# Interface_BUS.net
KiCad netlist of a schematic drawn in Altium Designer
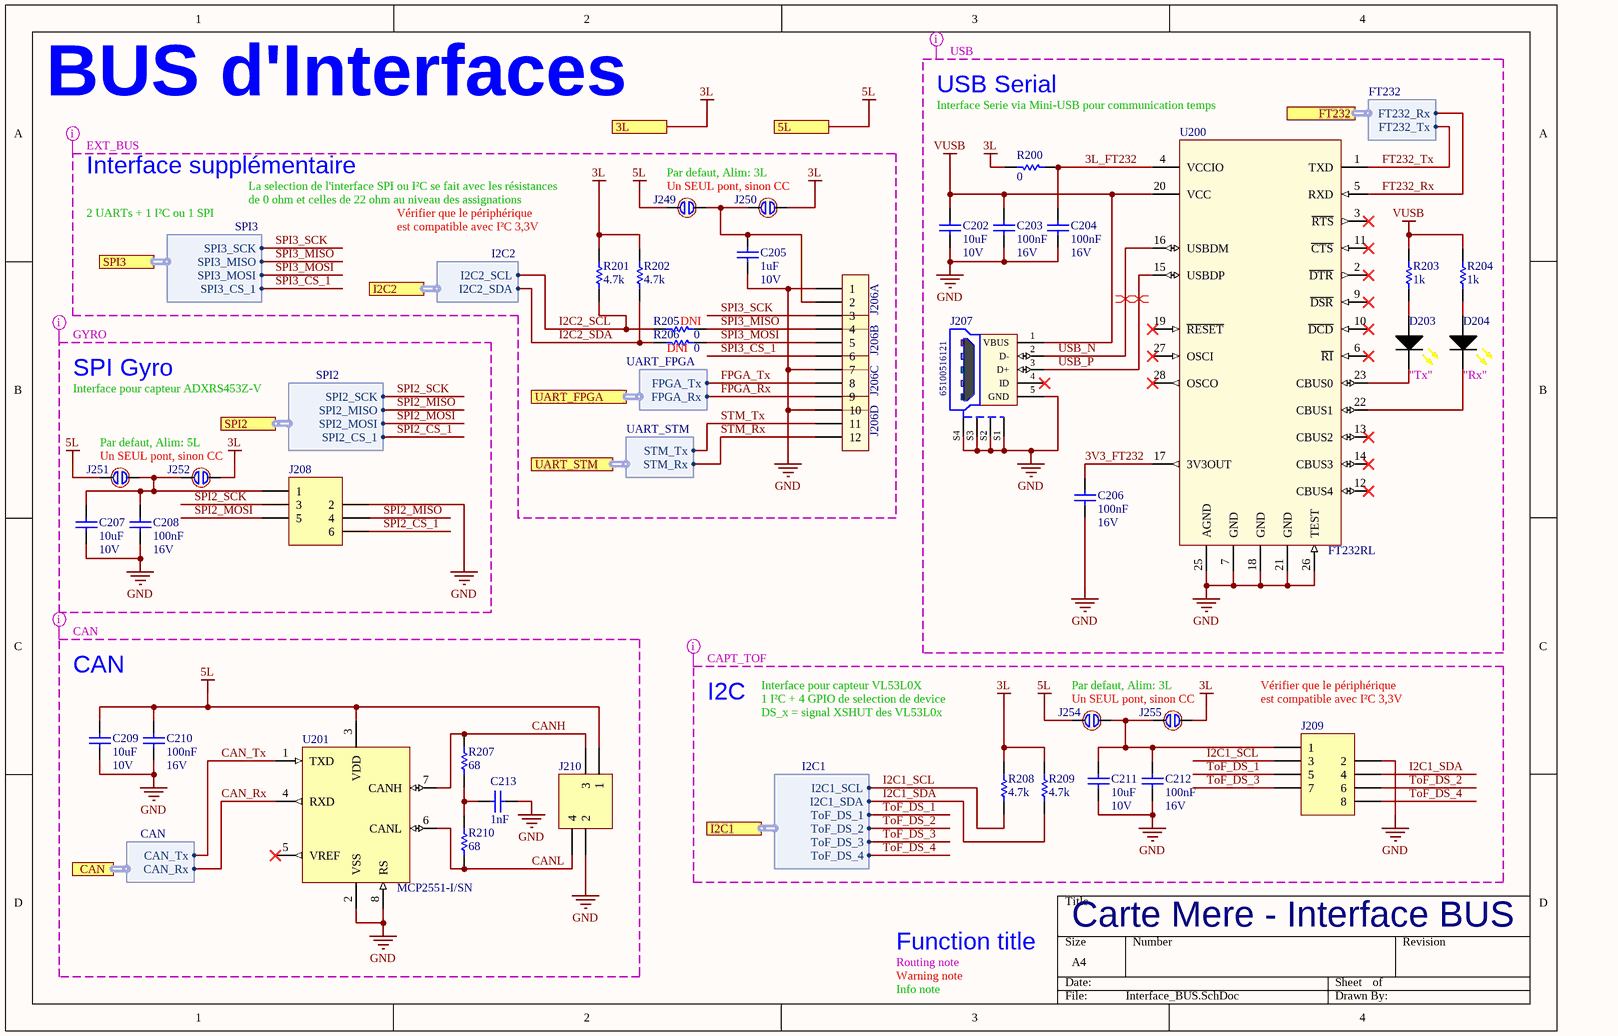
[diagram p0: Interface_BUS.SchDoc]

(export (version "E")
  (design (tool "Eeschema 10.0.6"))
  (components
    (comp (ref "C202")
      (value "10uF")
      (footprint "WCAP-CSGP_0805, 2x1.25x1.25")
      (description "CAP CER 10uF 10V X7R 0805")
      (fields
        (field (name "MANUFACTURER") "Wurth Elektronik")
        (field (name "MANUFACTURER PART NUMBER") "885012207026")
        (field (name "RATEDVOLTAGE") "10V")
      )
      (libsource (lib "Condensateur") (part "WCAP-CSGP, 885012207026"))
    )
    (comp (ref "C203")
      (value "100nF")
      (footprint "WCAP-CSGP_0402, 1x0.5x0.5")
      (description "CAP CER 100nF 16V X7R 0402")
      (fields
        (field (name "MANUFACTURER") "Wurth Elektronik")
        (field (name "MANUFACTURER PART NUMBER") "885012205037")
        (field (name "RATEDVOLTAGE") "16V")
      )
      (libsource (lib "Condensateur") (part "WCAP-CSGP, 885012205037"))
    )
    (comp (ref "C204")
      (value "100nF")
      (footprint "WCAP-CSGP_0402, 1x0.5x0.5")
      (description "CAP CER 100nF 16V X7R 0402")
      (fields
        (field (name "MANUFACTURER") "Wurth Elektronik")
        (field (name "MANUFACTURER PART NUMBER") "885012205037")
        (field (name "RATEDVOLTAGE") "16V")
      )
      (libsource (lib "Condensateur") (part "WCAP-CSGP, 885012205037"))
    )
    (comp (ref "C205")
      (value "1uF")
      (footprint "WCAP-CSGP_0402, 1x0.5x0.5")
      (description "CAP CER 1UF 10V X5R 0402")
      (fields
        (field (name "MANUFACTURER") "Wurth Elektronik")
        (field (name "MANUFACTURER PART NUMBER") "885012105012")
        (field (name "RATEDVOLTAGE") "10V")
      )
      (libsource (lib "Condensateur") (part "WCAP-CSGP, 885012105012"))
    )
    (comp (ref "C206")
      (value "100nF")
      (footprint "WCAP-CSGP_0402, 1x0.5x0.5")
      (description "CAP CER 100nF 16V X7R 0402")
      (fields
        (field (name "MANUFACTURER") "Wurth Elektronik")
        (field (name "MANUFACTURER PART NUMBER") "885012205037")
        (field (name "RATEDVOLTAGE") "16V")
      )
      (libsource (lib "Condensateur") (part "WCAP-CSGP, 885012205037"))
    )
    (comp (ref "C207")
      (value "10uF")
      (footprint "WCAP-CSGP_0805, 2x1.25x1.25")
      (description "CAP CER 10uF 10V X7R 0805")
      (fields
        (field (name "MANUFACTURER") "Wurth Elektronik")
        (field (name "MANUFACTURER PART NUMBER") "885012207026")
        (field (name "RATEDVOLTAGE") "10V")
      )
      (libsource (lib "Condensateur") (part "WCAP-CSGP, 885012207026"))
    )
    (comp (ref "C208")
      (value "100nF")
      (footprint "WCAP-CSGP_0402, 1x0.5x0.5")
      (description "CAP CER 100nF 16V X7R 0402")
      (fields
        (field (name "MANUFACTURER") "Wurth Elektronik")
        (field (name "MANUFACTURER PART NUMBER") "885012205037")
        (field (name "RATEDVOLTAGE") "16V")
      )
      (libsource (lib "Condensateur") (part "WCAP-CSGP, 885012205037"))
    )
    (comp (ref "C209")
      (value "10uF")
      (footprint "WCAP-CSGP_0805, 2x1.25x1.25")
      (description "CAP CER 10uF 10V X7R 0805")
      (fields
        (field (name "MANUFACTURER") "Wurth Elektronik")
        (field (name "MANUFACTURER PART NUMBER") "885012207026")
        (field (name "RATEDVOLTAGE") "10V")
      )
      (libsource (lib "Condensateur") (part "WCAP-CSGP, 885012207026"))
    )
    (comp (ref "C210")
      (value "100nF")
      (footprint "WCAP-CSGP_0402, 1x0.5x0.5")
      (description "CAP CER 100nF 16V X7R 0402")
      (fields
        (field (name "MANUFACTURER") "Wurth Elektronik")
        (field (name "MANUFACTURER PART NUMBER") "885012205037")
        (field (name "RATEDVOLTAGE") "16V")
      )
      (libsource (lib "Condensateur") (part "WCAP-CSGP, 885012205037"))
    )
    (comp (ref "C211")
      (value "10uF")
      (footprint "WCAP-CSGP_0805, 2x1.25x1.25")
      (description "CAP CER 10uF 10V X7R 0805")
      (fields
        (field (name "MANUFACTURER") "Wurth Elektronik")
        (field (name "MANUFACTURER PART NUMBER") "885012207026")
        (field (name "RATEDVOLTAGE") "10V")
      )
      (libsource (lib "Condensateur") (part "WCAP-CSGP, 885012207026"))
    )
    (comp (ref "C212")
      (value "100nF")
      (footprint "WCAP-CSGP_0402, 1x0.5x0.5")
      (description "CAP CER 100nF 16V X7R 0402")
      (fields
        (field (name "MANUFACTURER") "Wurth Elektronik")
        (field (name "MANUFACTURER PART NUMBER") "885012205037")
        (field (name "RATEDVOLTAGE") "16V")
      )
      (libsource (lib "Condensateur") (part "WCAP-CSGP, 885012205037"))
    )
    (comp (ref "C213")
      (value "1nF")
      (footprint "WCAP-CSGP_0402, 1x0.5x0.5")
      (description "CAP CER 1nF 50V X7R 0402")
      (fields
        (field (name "MANUFACTURER") "Wurth Elektronik")
        (field (name "MANUFACTURER PART NUMBER") "885012205061")
      )
      (libsource (lib "Condensateur") (part "WCAP-CSGP, 885012205061"))
    )
    (comp (ref "D203")
      (value "150060YS75000")
      (footprint "SMCW_0603")
      (description "SMD mono-color Chip LED, WL-SMCW, Yellow")
      (fields (field (name "MANUFACTURER") "Wurth Elektronik"))
      (libsource (lib "Opto") (part "WL-SMCW 0603  150060YS75000"))
    )
    (comp (ref "D204")
      (value "150060YS75000")
      (footprint "SMCW_0603")
      (description "SMD mono-color Chip LED, WL-SMCW, Yellow")
      (fields (field (name "MANUFACTURER") "Wurth Elektronik"))
      (libsource (lib "Opto") (part "WL-SMCW 0603  150060YS75000"))
    )
    (comp (ref "J206")
      (value "TSW-104-08-F-T-RA")
      (footprint "TSW-104-08-F-T-RA")
      (description "CONN HEADER R/A 3L x 4POS 2.54MM")
      (fields (field (name "MANUFACTURER") "SAMTEC"))
      (libsource (lib "Connecteurs") (part "TSW-104-08-F-T-RA"))
    )
    (comp (ref "J207")
      (value "65100516121")
      (footprint "65100516121")
      (description "Mini USB 2.0 Type B, Receptacle, Horizontal, SMT")
      (fields (field (name "MANUFACTURER") "Wurth Elektronik"))
      (libsource (lib "Connecteurs") (part "65100516121"))
    )
    (comp (ref "J208")
      (value "690367280676")
      (footprint "690367280676")
      (description "WR-MM 6p Female SMT Connector with Polarization")
      (fields (field (name "MANUFACTURER") "Wurth Electronics Inc."))
      (libsource (lib "Connecteurs") (part "690367280676"))
    )
    (comp (ref "J209")
      (value "690367280876")
      (footprint "690367280876")
      (description "WR-MM 8p Female SMT Connector with Polarization")
      (fields (field (name "MANUFACTURER") "Wurth Electronics Inc."))
      (libsource (lib "Connecteurs") (part "690367280876"))
    )
    (comp (ref "J210")
      (value "690367280476")
      (footprint "690367280476")
      (description "WR-MM 4p Female SMT Connector with Polarization")
      (fields (field (name "MANUFACTURER") "Wurth Electronics Inc."))
      (libsource (lib "Connecteurs") (part "690367280476"))
    )
    (comp (ref "J249")
      (value "open")
      (footprint "CAVALIER")
      (description "Cavalier soudure \"ouvert\", pastille fendue 1.2mm")
      (libsource (lib "Divers") (part "CAVALIER_DOT"))
    )
    (comp (ref "J250")
      (value "open")
      (footprint "CAVALIER")
      (description "Cavalier soudure \"ouvert\", pastille fendue 1.2mm")
      (libsource (lib "Divers") (part "CAVALIER_DOT"))
    )
    (comp (ref "J251")
      (value "open")
      (footprint "CAVALIER")
      (description "Cavalier soudure \"ouvert\", pastille fendue 1.2mm")
      (libsource (lib "Divers") (part "CAVALIER_DOT"))
    )
    (comp (ref "J252")
      (value "open")
      (footprint "CAVALIER")
      (description "Cavalier soudure \"ouvert\", pastille fendue 1.2mm")
      (libsource (lib "Divers") (part "CAVALIER_DOT"))
    )
    (comp (ref "J254")
      (value "open")
      (footprint "CAVALIER")
      (description "Cavalier soudure \"ouvert\", pastille fendue 1.2mm")
      (libsource (lib "Divers") (part "CAVALIER_DOT"))
    )
    (comp (ref "J255")
      (value "open")
      (footprint "CAVALIER")
      (description "Cavalier soudure \"ouvert\", pastille fendue 1.2mm")
      (libsource (lib "Divers") (part "CAVALIER_DOT"))
    )
    (comp (ref "R200")
      (value "0")
      (footprint "RESC1608X06N")
      (description "RES SMD 0 OHM 1% 1/10W 0603")
      (fields
        (field (name "MANUFACTURER") "Yageo")
        (field (name "MANUFACTURER PART NUMBER") "RC0603FR-070RL")
      )
      (libsource (lib "Resistance") (part "RC0603FR-070RL"))
    )
    (comp (ref "R201")
      (value "4.7k")
      (footprint "RESC1005X04N")
      (description "RES SMD 4K7 OHM 1% 1/16W 0402")
      (fields (field (name "POWER") "63mW") (field (name "MANUFACTURER") "Yageo"))
      (libsource (lib "Resistance") (part "RC0402FR-074K7L"))
    )
    (comp (ref "R202")
      (value "4.7k")
      (footprint "RESC1005X04N")
      (description "RES SMD 4K7 OHM 1% 1/16W 0402")
      (fields (field (name "POWER") "63mW") (field (name "MANUFACTURER") "Yageo"))
      (libsource (lib "Resistance") (part "RC0402FR-074K7L"))
    )
    (comp (ref "R203")
      (value "1k")
      (footprint "RESC1005X04N")
      (description "RES SMD 1K OHM 1% 1/16W 0402")
      (fields (field (name "POWER") "63mW") (field (name "MANUFACTURER") "Yageo"))
      (libsource (lib "Resistance") (part "RC0402FR-071KL"))
    )
    (comp (ref "R204")
      (value "1k")
      (footprint "RESC1005X04N")
      (description "RES SMD 1K OHM 1% 1/16W 0402")
      (fields (field (name "POWER") "63mW") (field (name "MANUFACTURER") "Yageo"))
      (libsource (lib "Resistance") (part "RC0402FR-071KL"))
    )
    (comp (ref "R205")
      (value "0")
      (footprint "RESC1608X06N")
      (description "RES SMD 0 OHM 1% 1/10W 0603")
      (fields
        (field (name "MANUFACTURER") "Yageo")
        (field (name "MANUFACTURER PART NUMBER") "RC0603FR-070RL")
      )
      (libsource (lib "Resistance") (part "RC0603FR-070RL"))
    )
    (comp (ref "R206")
      (value "0")
      (footprint "RESC1608X06N")
      (description "RES SMD 0 OHM 1% 1/10W 0603")
      (fields
        (field (name "MANUFACTURER") "Yageo")
        (field (name "MANUFACTURER PART NUMBER") "RC0603FR-070RL")
      )
      (libsource (lib "Resistance") (part "RC0603FR-070RL"))
    )
    (comp (ref "R207")
      (value "68")
      (footprint "RESC1608X06N")
      (description "RES SMD 68 OHM 1% 1/10W 0603")
      (fields
        (field (name "MANUFACTURER") "Yageo")
        (field (name "MANUFACTURER PART NUMBER") "RC0603FR-0768RL")
      )
      (libsource (lib "Resistance") (part "RC0603FR-0768RL"))
    )
    (comp (ref "R208")
      (value "4.7k")
      (footprint "RESC1005X04N")
      (description "RES SMD 4K7 OHM 1% 1/16W 0402")
      (fields (field (name "POWER") "63mW") (field (name "MANUFACTURER") "Yageo"))
      (libsource (lib "Resistance") (part "RC0402FR-074K7L"))
    )
    (comp (ref "R209")
      (value "4.7k")
      (footprint "RESC1005X04N")
      (description "RES SMD 4K7 OHM 1% 1/16W 0402")
      (fields (field (name "POWER") "63mW") (field (name "MANUFACTURER") "Yageo"))
      (libsource (lib "Resistance") (part "RC0402FR-074K7L"))
    )
    (comp (ref "R210")
      (value "68")
      (footprint "RESC1608X06N")
      (description "RES SMD 68 OHM 1% 1/10W 0603")
      (fields
        (field (name "MANUFACTURER") "Yageo")
        (field (name "MANUFACTURER PART NUMBER") "RC0603FR-0768RL")
      )
      (libsource (lib "Resistance") (part "RC0603FR-0768RL"))
    )
    (comp (ref "U200")
      (value "FT232RL")
      (footprint "SSOP28")
      (description "USB VERS UART CMS SSOP28 232")
      (fields (field (name "MANUFACTURER") "FTDI"))
      (libsource (lib "CI") (part "FT232RL"))
    )
    (comp (ref "U201")
      (value "MCP2551-I/SN")
      (footprint "SOIC127P600X175-8N")
      (description "IC TRANSCEIVER CAN HI-SPD 8-SOIC")
      (fields (field (name "MANUFACTURER") "Microchip Technology"))
      (libsource (lib "CI") (part "MCP2551-I/SN"))
    )
  )
  (nets
    (net (code "9") (name "/3L_FT232") (class "Default")
      (node (ref "C204") (pin "1") (pinfunction "1_1") (pintype "passive"))
      (node (ref "R200") (pin "2") (pinfunction "2_2") (pintype "passive"))
      (node (ref "U200") (pin "4") (pinfunction "VCCIO_4") (pintype "power_in"))
    )
    (net (code "10") (name "/3V3_FT232") (class "Default")
      (node (ref "C206") (pin "1") (pinfunction "1_1") (pintype "passive"))
      (node (ref "U200") (pin "17") (pinfunction "3V3OUT_17") (pintype "output"))
    )
    (net (code "11") (name "/CANH") (class "Default")
      (node (ref "J210") (pin "3") (pinfunction "3_3") (pintype "passive"))
      (node (ref "R207") (pin "2") (pinfunction "2_2") (pintype "passive"))
      (node (ref "U201") (pin "7") (pinfunction "CANH_7") (pintype "bidirectional"))
    )
    (net (code "12") (name "/CANL") (class "Default")
      (node (ref "J210") (pin "4") (pinfunction "4_4") (pintype "passive"))
      (node (ref "R210") (pin "1") (pinfunction "1_1") (pintype "passive"))
      (node (ref "U201") (pin "6") (pinfunction "CANL_6") (pintype "bidirectional"))
    )
    (net (code "13") (name "/CAN_Rx") (class "Default")
      (node (ref "U201") (pin "4") (pinfunction "RXD_4") (pintype "output"))
    )
    (net (code "14") (name "/CAN_Tx") (class "Default")
      (node (ref "U201") (pin "1") (pinfunction "TXD_1") (pintype "input"))
    )
    (net (code "15") (name "/FPGA_Rx") (class "Default")
      (node (ref "J206") (pin "9") (pinfunction "9_9") (pintype "passive"))
    )
    (net (code "16") (name "/FPGA_Tx") (class "Default")
      (node (ref "J206") (pin "8") (pinfunction "8_8") (pintype "passive"))
    )
    (net (code "17") (name "/FT232_Rx") (class "Default")
      (node (ref "U200") (pin "5") (pinfunction "RXD_5") (pintype "input"))
    )
    (net (code "18") (name "/FT232_Tx") (class "Default")
      (node (ref "U200") (pin "1") (pinfunction "TXD_1") (pintype "passive"))
    )
    (net (code "19") (name "/I2C1_SCL") (class "Default")
      (node (ref "J209") (pin "3") (pinfunction "3_3") (pintype "passive"))
      (node (ref "R208") (pin "1") (pinfunction "1_1") (pintype "passive"))
    )
    (net (code "20") (name "/I2C1_SDA") (class "Default")
      (node (ref "J209") (pin "4") (pinfunction "4_4") (pintype "passive"))
      (node (ref "R209") (pin "1") (pinfunction "1_1") (pintype "passive"))
    )
    (net (code "21") (name "/I2C2_SCL") (class "Default")
      (node (ref "R201") (pin "1") (pinfunction "1_1") (pintype "passive"))
      (node (ref "R205") (pin "1") (pinfunction "1_1") (pintype "passive"))
    )
    (net (code "22") (name "/I2C2_SDA") (class "Default")
      (node (ref "R202") (pin "1") (pinfunction "1_1") (pintype "passive"))
      (node (ref "R206") (pin "1") (pinfunction "1_1") (pintype "passive"))
    )
    (net (code "23") (name "/SPI2_CS_1") (class "Default")
      (node (ref "J208") (pin "6") (pinfunction "6_6") (pintype "passive"))
    )
    (net (code "24") (name "/SPI2_MISO") (class "Default")
      (node (ref "J208") (pin "4") (pinfunction "4_4") (pintype "passive"))
    )
    (net (code "25") (name "/SPI2_MOSI") (class "Default")
      (node (ref "J208") (pin "5") (pinfunction "5_5") (pintype "passive"))
    )
    (net (code "26") (name "/SPI2_SCK") (class "Default")
      (node (ref "J208") (pin "3") (pinfunction "3_3") (pintype "passive"))
    )
    (net (code "27") (name "/SPI3_CS_1") (class "Default")
      (node (ref "J206") (pin "6") (pinfunction "6_6") (pintype "passive"))
    )
    (net (code "28") (name "/SPI3_MISO") (class "Default")
      (node (ref "J206") (pin "4") (pinfunction "4_4") (pintype "passive"))
      (node (ref "R205") (pin "2") (pinfunction "2_2") (pintype "passive"))
    )
    (net (code "29") (name "/SPI3_MOSI") (class "Default")
      (node (ref "J206") (pin "5") (pinfunction "5_5") (pintype "passive"))
      (node (ref "R206") (pin "2") (pinfunction "2_2") (pintype "passive"))
    )
    (net (code "30") (name "/SPI3_SCK") (class "Default")
      (node (ref "J206") (pin "3") (pinfunction "3_3") (pintype "passive"))
    )
    (net (code "31") (name "/STM_Rx") (class "Default")
      (node (ref "J206") (pin "12") (pinfunction "12_12") (pintype "passive"))
    )
    (net (code "32") (name "/STM_Tx") (class "Default")
      (node (ref "J206") (pin "11") (pinfunction "11_11") (pintype "passive"))
    )
    (net (code "33") (name "/ToF_DS_1") (class "Default")
      (node (ref "J209") (pin "5") (pinfunction "5_5") (pintype "passive"))
    )
    (net (code "34") (name "/ToF_DS_2") (class "Default")
      (node (ref "J209") (pin "6") (pinfunction "6_6") (pintype "passive"))
    )
    (net (code "35") (name "/ToF_DS_3") (class "Default")
      (node (ref "J209") (pin "7") (pinfunction "7_7") (pintype "passive"))
    )
    (net (code "36") (name "/ToF_DS_4") (class "Default")
      (node (ref "J209") (pin "8") (pinfunction "8_8") (pintype "passive"))
    )
    (net (code "37") (name "/USB_N") (class "Default")
      (node (ref "J207") (pin "2") (pinfunction "D-_2") (pintype "bidirectional"))
      (node (ref "U200") (pin "16") (pinfunction "USBDM_16") (pintype "bidirectional"))
    )
    (net (code "38") (name "/USB_P") (class "Default")
      (node (ref "J207") (pin "3") (pinfunction "D+_3") (pintype "bidirectional"))
      (node (ref "U200") (pin "15") (pinfunction "USBDP_15") (pintype "bidirectional"))
    )
    (net (code "47") (name "3L") (class "Default")
      (node (ref "J250") (pin "2") (pinfunction "2_2") (pintype "passive"))
      (node (ref "J252") (pin "2") (pinfunction "2_2") (pintype "passive"))
      (node (ref "J255") (pin "2") (pinfunction "2_2") (pintype "passive"))
      (node (ref "R200") (pin "1") (pinfunction "1_1") (pintype "passive"))
      (node (ref "R201") (pin "2") (pinfunction "2_2") (pintype "passive"))
      (node (ref "R202") (pin "2") (pinfunction "2_2") (pintype "passive"))
      (node (ref "R208") (pin "2") (pinfunction "2_2") (pintype "passive"))
      (node (ref "R209") (pin "2") (pinfunction "2_2") (pintype "passive"))
    )
    (net (code "48") (name "5L") (class "Default")
      (node (ref "C209") (pin "1") (pinfunction "1_1") (pintype "passive"))
      (node (ref "C210") (pin "1") (pinfunction "1_1") (pintype "passive"))
      (node (ref "J210") (pin "1") (pinfunction "1_1") (pintype "passive"))
      (node (ref "J249") (pin "1") (pinfunction "1_1") (pintype "passive"))
      (node (ref "J251") (pin "1") (pinfunction "1_1") (pintype "passive"))
      (node (ref "J254") (pin "1") (pinfunction "1_1") (pintype "passive"))
      (node (ref "U201") (pin "3") (pinfunction "VDD_3") (pintype "power_in"))
    )
    (net (code "49") (name "GND") (class "Default")
      (node (ref "C202") (pin "2") (pinfunction "2_2") (pintype "passive"))
      (node (ref "C203") (pin "2") (pinfunction "2_2") (pintype "passive"))
      (node (ref "C204") (pin "2") (pinfunction "2_2") (pintype "passive"))
      (node (ref "C205") (pin "2") (pinfunction "2_2") (pintype "passive"))
      (node (ref "C206") (pin "2") (pinfunction "2_2") (pintype "passive"))
      (node (ref "C207") (pin "2") (pinfunction "2_2") (pintype "passive"))
      (node (ref "C208") (pin "2") (pinfunction "2_2") (pintype "passive"))
      (node (ref "C209") (pin "2") (pinfunction "2_2") (pintype "passive"))
      (node (ref "C210") (pin "2") (pinfunction "2_2") (pintype "passive"))
      (node (ref "C211") (pin "2") (pinfunction "2_2") (pintype "passive"))
      (node (ref "C212") (pin "2") (pinfunction "2_2") (pintype "passive"))
      (node (ref "C213") (pin "2") (pinfunction "2_2") (pintype "passive"))
      (node (ref "J206") (pin "1") (pinfunction "1_1") (pintype "passive"))
      (node (ref "J206") (pin "10") (pinfunction "10_10") (pintype "passive"))
      (node (ref "J206") (pin "7") (pinfunction "7_7") (pintype "passive"))
      (node (ref "J207") (pin "5") (pinfunction "GND_5") (pintype "passive"))
      (node (ref "J207") (pin "S1") (pinfunction "Shield_S1") (pintype "passive"))
      (node (ref "J207") (pin "S2") (pinfunction "Shield_S2") (pintype "passive"))
      (node (ref "J207") (pin "S3") (pinfunction "Shield_S3") (pintype "passive"))
      (node (ref "J207") (pin "S4") (pinfunction "Shield_S4") (pintype "passive"))
      (node (ref "J208") (pin "2") (pinfunction "2_2") (pintype "passive"))
      (node (ref "J209") (pin "2") (pinfunction "2_2") (pintype "passive"))
      (node (ref "J210") (pin "2") (pinfunction "2_2") (pintype "passive"))
      (node (ref "U200") (pin "18") (pinfunction "GND_18") (pintype "power_in"))
      (node (ref "U200") (pin "21") (pinfunction "GND_21") (pintype "power_in"))
      (node (ref "U200") (pin "25") (pinfunction "AGND_25") (pintype "power_in"))
      (node (ref "U200") (pin "26") (pinfunction "TEST_26") (pintype "input"))
      (node (ref "U200") (pin "7") (pinfunction "GND_7") (pintype "power_in"))
      (node (ref "U201") (pin "2") (pinfunction "VSS_2") (pintype "power_in"))
      (node (ref "U201") (pin "8") (pinfunction "RS_8") (pintype "input"))
    )
    (net (code "50") (name "Net-(C205-Pad1)") (class "Default")
      (node (ref "C205") (pin "1") (pinfunction "1_1") (pintype "passive"))
      (node (ref "J206") (pin "2") (pinfunction "2_2") (pintype "passive"))
      (node (ref "J249") (pin "2") (pinfunction "2_2") (pintype "passive"))
      (node (ref "J250") (pin "1") (pinfunction "1_1") (pintype "passive"))
    )
    (net (code "51") (name "Net-(C207-Pad1)") (class "Default")
      (node (ref "C207") (pin "1") (pinfunction "1_1") (pintype "passive"))
      (node (ref "C208") (pin "1") (pinfunction "1_1") (pintype "passive"))
      (node (ref "J208") (pin "1") (pinfunction "1_1") (pintype "passive"))
      (node (ref "J251") (pin "2") (pinfunction "2_2") (pintype "passive"))
      (node (ref "J252") (pin "1") (pinfunction "1_1") (pintype "passive"))
    )
    (net (code "52") (name "Net-(C211-Pad1)") (class "Default")
      (node (ref "C211") (pin "1") (pinfunction "1_1") (pintype "passive"))
      (node (ref "C212") (pin "1") (pinfunction "1_1") (pintype "passive"))
      (node (ref "J209") (pin "1") (pinfunction "1_1") (pintype "passive"))
      (node (ref "J254") (pin "2") (pinfunction "2_2") (pintype "passive"))
      (node (ref "J255") (pin "1") (pinfunction "1_1") (pintype "passive"))
    )
    (net (code "53") (name "Net-(C213-Pad1)") (class "Default")
      (node (ref "C213") (pin "1") (pinfunction "1_1") (pintype "passive"))
      (node (ref "R207") (pin "1") (pinfunction "1_1") (pintype "passive"))
      (node (ref "R210") (pin "2") (pinfunction "2_2") (pintype "passive"))
    )
    (net (code "54") (name "Net-(D203-A)") (class "Default")
      (node (ref "D203") (pin "2") (pinfunction "A_2") (pintype "passive"))
      (node (ref "R203") (pin "2") (pinfunction "2_2") (pintype "passive"))
    )
    (net (code "55") (name "Net-(D203-C)") (class "Default")
      (node (ref "D203") (pin "1") (pinfunction "C_1") (pintype "passive"))
      (node (ref "U200") (pin "23") (pinfunction "CBUS0_23") (pintype "bidirectional"))
    )
    (net (code "56") (name "Net-(D204-A)") (class "Default")
      (node (ref "D204") (pin "2") (pinfunction "A_2") (pintype "passive"))
      (node (ref "R204") (pin "2") (pinfunction "2_2") (pintype "passive"))
    )
    (net (code "57") (name "Net-(D204-C)") (class "Default")
      (node (ref "D204") (pin "1") (pinfunction "C_1") (pintype "passive"))
      (node (ref "U200") (pin "22") (pinfunction "CBUS1_22") (pintype "bidirectional"))
    )
    (net (code "58") (name "VUSB") (class "Default")
      (node (ref "C202") (pin "1") (pinfunction "1_1") (pintype "passive"))
      (node (ref "C203") (pin "1") (pinfunction "1_1") (pintype "passive"))
      (node (ref "J207") (pin "1") (pinfunction "VBUS_1") (pintype "passive"))
      (node (ref "R203") (pin "1") (pinfunction "1_1") (pintype "passive"))
      (node (ref "R204") (pin "1") (pinfunction "1_1") (pintype "passive"))
      (node (ref "U200") (pin "20") (pinfunction "VCC_20") (pintype "power_in"))
    )
    (net (code "59") (name "unconnected-(J207-ID-Pad4)") (class "Default")
      (node (ref "J207") (pin "4") (pinfunction "ID_4") (pintype "passive+no_connect"))
    )
    (net (code "60") (name "unconnected-(U200-CBUS2-Pad13)") (class "Default")
      (node (ref "U200") (pin "13") (pinfunction "CBUS2_13") (pintype "bidirectional+no_connect"))
    )
    (net (code "61") (name "unconnected-(U200-CBUS3-Pad14)") (class "Default")
      (node (ref "U200") (pin "14") (pinfunction "CBUS3_14") (pintype "bidirectional+no_connect"))
    )
    (net (code "62") (name "unconnected-(U200-CBUS4-Pad12)") (class "Default")
      (node (ref "U200") (pin "12") (pinfunction "CBUS4_12") (pintype "bidirectional+no_connect"))
    )
    (net (code "63") (name "unconnected-(U200-OSCI-Pad27)") (class "Default")
      (node (ref "U200") (pin "27") (pinfunction "OSCI_27") (pintype "input+no_connect"))
    )
    (net (code "64") (name "unconnected-(U200-OSCO-Pad28)") (class "Default")
      (node (ref "U200") (pin "28") (pinfunction "OSCO_28") (pintype "output+no_connect"))
    )
    (net (code "65") (name "unconnected-(U200-~{CTS}-Pad11)") (class "Default")
      (node (ref "U200") (pin "11") (pinfunction "~{CTS}_11") (pintype "input+no_connect"))
    )
    (net (code "66") (name "unconnected-(U200-~{DCD}-Pad10)") (class "Default")
      (node (ref "U200") (pin "10") (pinfunction "~{DCD}_10") (pintype "input+no_connect"))
    )
    (net (code "67") (name "unconnected-(U200-~{DSR}-Pad9)") (class "Default")
      (node (ref "U200") (pin "9") (pinfunction "~{DSR}_9") (pintype "input+no_connect"))
    )
    (net (code "68") (name "unconnected-(U200-~{DTR}-Pad2)") (class "Default")
      (node (ref "U200") (pin "2") (pinfunction "~{DTR}_2") (pintype "output+no_connect"))
    )
    (net (code "69") (name "unconnected-(U200-~{RESET}-Pad19)") (class "Default")
      (node (ref "U200") (pin "19") (pinfunction "~{RESET}_19") (pintype "input+no_connect"))
    )
    (net (code "70") (name "unconnected-(U200-~{RI}-Pad6)") (class "Default")
      (node (ref "U200") (pin "6") (pinfunction "~{RI}_6") (pintype "input+no_connect"))
    )
    (net (code "71") (name "unconnected-(U200-~{RTS}-Pad3)") (class "Default")
      (node (ref "U200") (pin "3") (pinfunction "~{RTS}_3") (pintype "output+no_connect"))
    )
    (net (code "72") (name "unconnected-(U201-VREF-Pad5)") (class "Default")
      (node (ref "U201") (pin "5") (pinfunction "VREF_5") (pintype "output+no_connect"))
    )
  )
)
